# thermometer.net
KiCad netlist of a schematic drawn in EAGLE
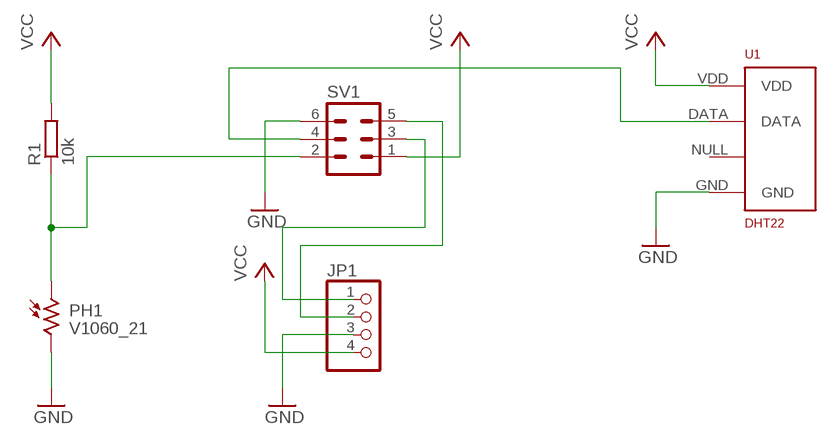
[diagram p0: schematic, sheet 1]

(export (version "E")
  (design (tool "Eeschema 10.0.6"))
  (components
    (comp (ref "JP1")
      (value "PINHD-1X4")
      (footprint "eagle-import:1X04")
      (libsource (lib "eagle-import") (part "PINHD-1X4"))
    )
    (comp (ref "PH1")
      (value "V1060_21")
      (footprint "eagle-import:TO-5_V10")
      (libsource (lib "eagle-import") (part "?1060V_21"))
    )
    (comp (ref "R1")
      (value "10k")
      (footprint "eagle-import:0207_12")
      (libsource (lib "eagle-import") (part "R-EU_0207/12"))
    )
    (comp (ref "SV1")
      (value "ML6")
      (footprint "eagle-import:ML6")
      (libsource (lib "eagle-import") (part "ML6"))
    )
    (comp (ref "U1")
      (value "DHT22")
      (footprint "eagle-import:RHT03_DHT-22_RA")
      (libsource (lib "eagle-import") (part "RHT03_DHT-22_AM2302RA"))
    )
  )
  (nets
    (net (code "1") (name "GND") (class "Default")
      (node (ref "JP1") (pin "3") (pinfunction "3_3") (pintype "passive"))
      (node (ref "PH1") (pin "2") (pinfunction "2_2") (pintype "passive"))
      (node (ref "SV1") (pin "6") (pinfunction "6_6") (pintype "passive"))
      (node (ref "U1") (pin "GND") (pinfunction "GND_GND") (pintype "power_in"))
    )
    (net (code "2") (name "Net-(JP1-Pad1)") (class "Default")
      (node (ref "JP1") (pin "1") (pinfunction "1_1") (pintype "passive"))
      (node (ref "SV1") (pin "3") (pinfunction "3_3") (pintype "passive"))
    )
    (net (code "3") (name "Net-(JP1-Pad2)") (class "Default")
      (node (ref "JP1") (pin "2") (pinfunction "2_2") (pintype "passive"))
      (node (ref "SV1") (pin "5") (pinfunction "5_5") (pintype "passive"))
    )
    (net (code "4") (name "Net-(PH1-Pad1)") (class "Default")
      (node (ref "PH1") (pin "1") (pinfunction "1_1") (pintype "passive"))
      (node (ref "R1") (pin "1") (pinfunction "1_1") (pintype "passive"))
      (node (ref "SV1") (pin "2") (pinfunction "2_2") (pintype "passive"))
    )
    (net (code "5") (name "Net-(SV1-Pad4)") (class "Default")
      (node (ref "SV1") (pin "4") (pinfunction "4_4") (pintype "passive"))
      (node (ref "U1") (pin "DATA") (pinfunction "DATA_DATA") (pintype "bidirectional"))
    )
    (net (code "6") (name "VCC") (class "Default")
      (node (ref "JP1") (pin "4") (pinfunction "4_4") (pintype "passive"))
      (node (ref "R1") (pin "2") (pinfunction "2_2") (pintype "passive"))
      (node (ref "SV1") (pin "1") (pinfunction "1_1") (pintype "passive"))
      (node (ref "U1") (pin "VDD") (pinfunction "VDD_VDD") (pintype "power_in"))
    )
    (net (code "7") (name "unconnected-(U1-PadNULL)") (class "Default")
      (node (ref "U1") (pin "NULL") (pinfunction "NULL_NULL") (pintype "no_connect"))
    )
  )
)
